# power_board_uC.net
KiCad netlist of a schematic drawn in Altium Designer
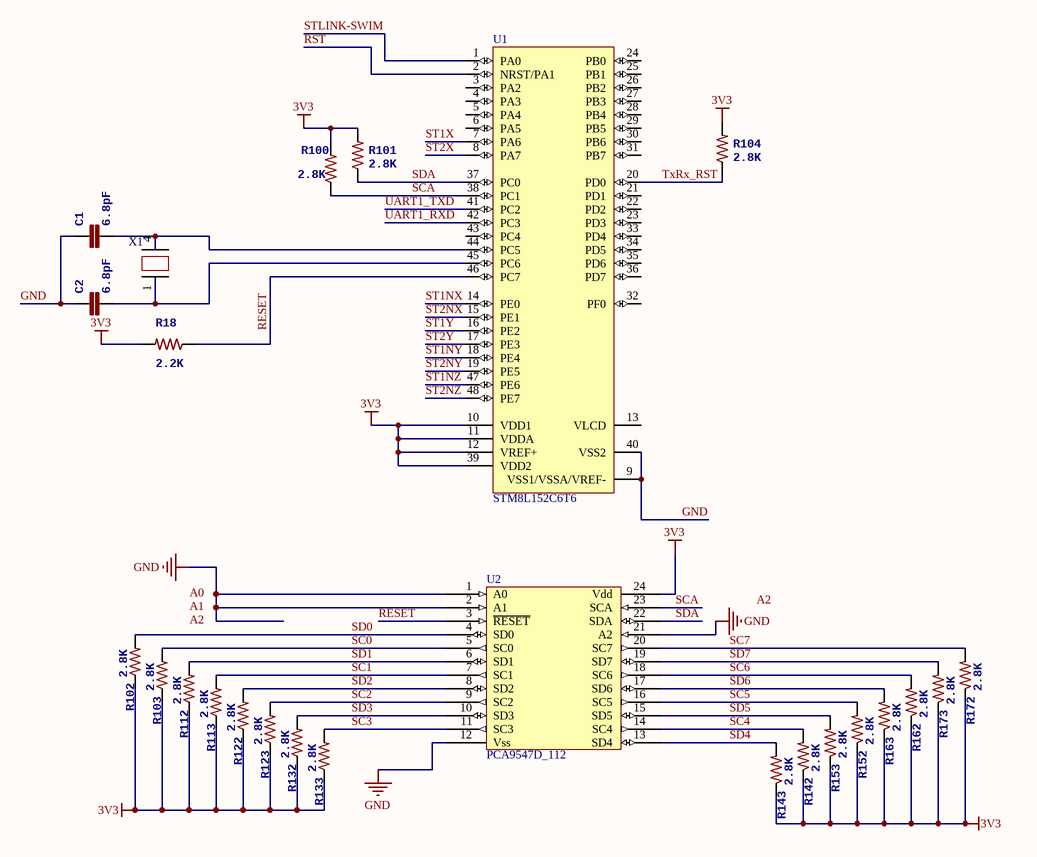
[diagram p0: power_board_uC.SchDoc]

(export (version "E")
  (design (tool "Eeschema 10.0.6"))
  (components
    (comp (ref "C1")
      (value "6.8pF")
      (footprint "0402-CAP")
      (libsource (lib "yusend_power") (part "CAP0402-6_8pF"))
    )
    (comp (ref "C2")
      (value "6.8pF")
      (footprint "0402-CAP")
      (libsource (lib "yusend_power") (part "CAP0402-6_8pF"))
    )
    (comp (ref "R18")
      (value "2.2K")
      (footprint "0805")
      (fields
        (field (name "MANUFACTURER") "TE Connectivity")
        (field (name "MANUFACTURER PART NUMBER") "1625856-2")
        (field (name "TOLERANCE") "±10%")
      )
      (libsource (lib "yusend_power") (part "RES_0805_2k2"))
    )
    (comp (ref "R100")
      (value "2.8K")
      (footprint "0805")
      (fields
        (field (name "MANUFACTURER") "TE Connectivity")
        (field (name "MANUFACTURER PART NUMBER") "1625856-2")
        (field (name "TOLERANCE") "±10%")
      )
      (libsource (lib "yusend_power") (part "RES_0805_2k8"))
    )
    (comp (ref "R101")
      (value "2.8K")
      (footprint "0805")
      (fields
        (field (name "MANUFACTURER") "TE Connectivity")
        (field (name "MANUFACTURER PART NUMBER") "1625856-2")
        (field (name "TOLERANCE") "±10%")
      )
      (libsource (lib "yusend_power") (part "RES_0805_2k8"))
    )
    (comp (ref "R102")
      (value "2.8K")
      (footprint "0805")
      (fields
        (field (name "MANUFACTURER") "TE Connectivity")
        (field (name "MANUFACTURER PART NUMBER") "1625856-2")
        (field (name "TOLERANCE") "±10%")
      )
      (libsource (lib "yusend_power") (part "RES_0805_2k8"))
    )
    (comp (ref "R103")
      (value "2.8K")
      (footprint "0805")
      (fields
        (field (name "MANUFACTURER") "TE Connectivity")
        (field (name "MANUFACTURER PART NUMBER") "1625856-2")
        (field (name "TOLERANCE") "±10%")
      )
      (libsource (lib "yusend_power") (part "RES_0805_2k8"))
    )
    (comp (ref "R104")
      (value "2.8K")
      (footprint "0805")
      (fields
        (field (name "MANUFACTURER") "TE Connectivity")
        (field (name "MANUFACTURER PART NUMBER") "1625856-2")
        (field (name "TOLERANCE") "±10%")
      )
      (libsource (lib "yusend_power") (part "RES_0805_2k8"))
    )
    (comp (ref "R112")
      (value "2.8K")
      (footprint "0805")
      (fields
        (field (name "MANUFACTURER") "TE Connectivity")
        (field (name "MANUFACTURER PART NUMBER") "1625856-2")
        (field (name "TOLERANCE") "±10%")
      )
      (libsource (lib "yusend_power") (part "RES_0805_2k8"))
    )
    (comp (ref "R113")
      (value "2.8K")
      (footprint "0805")
      (fields
        (field (name "MANUFACTURER") "TE Connectivity")
        (field (name "MANUFACTURER PART NUMBER") "1625856-2")
        (field (name "TOLERANCE") "±10%")
      )
      (libsource (lib "yusend_power") (part "RES_0805_2k8"))
    )
    (comp (ref "R122")
      (value "2.8K")
      (footprint "0805")
      (fields
        (field (name "MANUFACTURER") "TE Connectivity")
        (field (name "MANUFACTURER PART NUMBER") "1625856-2")
        (field (name "TOLERANCE") "±10%")
      )
      (libsource (lib "yusend_power") (part "RES_0805_2k8"))
    )
    (comp (ref "R123")
      (value "2.8K")
      (footprint "0805")
      (fields
        (field (name "MANUFACTURER") "TE Connectivity")
        (field (name "MANUFACTURER PART NUMBER") "1625856-2")
        (field (name "TOLERANCE") "±10%")
      )
      (libsource (lib "yusend_power") (part "RES_0805_2k8"))
    )
    (comp (ref "R132")
      (value "2.8K")
      (footprint "0805")
      (fields
        (field (name "MANUFACTURER") "TE Connectivity")
        (field (name "MANUFACTURER PART NUMBER") "1625856-2")
        (field (name "TOLERANCE") "±10%")
      )
      (libsource (lib "yusend_power") (part "RES_0805_2k8"))
    )
    (comp (ref "R133")
      (value "2.8K")
      (footprint "0805")
      (fields
        (field (name "MANUFACTURER") "TE Connectivity")
        (field (name "MANUFACTURER PART NUMBER") "1625856-2")
        (field (name "TOLERANCE") "±10%")
      )
      (libsource (lib "yusend_power") (part "RES_0805_2k8"))
    )
    (comp (ref "R142")
      (value "2.8K")
      (footprint "0805")
      (fields
        (field (name "MANUFACTURER") "TE Connectivity")
        (field (name "MANUFACTURER PART NUMBER") "1625856-2")
        (field (name "TOLERANCE") "±10%")
      )
      (libsource (lib "yusend_power") (part "RES_0805_2k8"))
    )
    (comp (ref "R143")
      (value "2.8K")
      (footprint "0805")
      (fields
        (field (name "MANUFACTURER") "TE Connectivity")
        (field (name "MANUFACTURER PART NUMBER") "1625856-2")
        (field (name "TOLERANCE") "±10%")
      )
      (libsource (lib "yusend_power") (part "RES_0805_2k8"))
    )
    (comp (ref "R152")
      (value "2.8K")
      (footprint "0805")
      (fields
        (field (name "MANUFACTURER") "TE Connectivity")
        (field (name "MANUFACTURER PART NUMBER") "1625856-2")
        (field (name "TOLERANCE") "±10%")
      )
      (libsource (lib "yusend_power") (part "RES_0805_2k8"))
    )
    (comp (ref "R153")
      (value "2.8K")
      (footprint "0805")
      (fields
        (field (name "MANUFACTURER") "TE Connectivity")
        (field (name "MANUFACTURER PART NUMBER") "1625856-2")
        (field (name "TOLERANCE") "±10%")
      )
      (libsource (lib "yusend_power") (part "RES_0805_2k8"))
    )
    (comp (ref "R162")
      (value "2.8K")
      (footprint "0805")
      (fields
        (field (name "MANUFACTURER") "TE Connectivity")
        (field (name "MANUFACTURER PART NUMBER") "1625856-2")
        (field (name "TOLERANCE") "±10%")
      )
      (libsource (lib "yusend_power") (part "RES_0805_2k8"))
    )
    (comp (ref "R163")
      (value "2.8K")
      (footprint "0805")
      (fields
        (field (name "MANUFACTURER") "TE Connectivity")
        (field (name "MANUFACTURER PART NUMBER") "1625856-2")
        (field (name "TOLERANCE") "±10%")
      )
      (libsource (lib "yusend_power") (part "RES_0805_2k8"))
    )
    (comp (ref "R172")
      (value "2.8K")
      (footprint "0805")
      (fields
        (field (name "MANUFACTURER") "TE Connectivity")
        (field (name "MANUFACTURER PART NUMBER") "1625856-2")
        (field (name "TOLERANCE") "±10%")
      )
      (libsource (lib "yusend_power") (part "RES_0805_2k8"))
    )
    (comp (ref "R173")
      (value "2.8K")
      (footprint "0805")
      (fields
        (field (name "MANUFACTURER") "TE Connectivity")
        (field (name "MANUFACTURER PART NUMBER") "1625856-2")
        (field (name "TOLERANCE") "±10%")
      )
      (libsource (lib "yusend_power") (part "RES_0805_2k8"))
    )
    (comp (ref "U1")
      (value "STM8L152C6T6")
      (footprint "LQFP48_M")
      (libsource (lib "Altium Content Vault") (part "MC-ARM-STM8L152-SQ48"))
    )
    (comp (ref "U2")
      (value "PCA9547D_112")
      (footprint "TSOP65P640X110-24N")
      (libsource (lib "yusend_power") (part "PCA9547D_112"))
    )
    (comp (ref "X1")
      (value "XTAL_32MHz")
      (footprint "SOJ550P350X254-4M")
      (libsource (lib "yusend_power") (part "XTAL_32MHz"))
    )
  )
  (nets
    (net (code "4") (name "/RESET") (class "Default")
      (node (ref "R18") (pin "1") (pinfunction "1_1") (pintype "passive"))
      (node (ref "U1") (pin "46") (pinfunction "PC7_46") (pintype "bidirectional"))
      (node (ref "U2") (pin "3") (pinfunction "~{RESET}_3") (pintype "input"))
    )
    (net (code "5") (name "/RST") (class "Default")
      (node (ref "U1") (pin "2") (pinfunction "NRST/PA1_2") (pintype "bidirectional"))
    )
    (net (code "6") (name "/SC0") (class "Default")
      (node (ref "R103") (pin "2") (pinfunction "2_2") (pintype "passive"))
      (node (ref "U2") (pin "5") (pinfunction "SC0_5") (pintype "output"))
    )
    (net (code "7") (name "/SC1") (class "Default")
      (node (ref "R113") (pin "2") (pinfunction "2_2") (pintype "passive"))
      (node (ref "U2") (pin "7") (pinfunction "SC1_7") (pintype "output"))
    )
    (net (code "8") (name "/SC2") (class "Default")
      (node (ref "R123") (pin "2") (pinfunction "2_2") (pintype "passive"))
      (node (ref "U2") (pin "9") (pinfunction "SC2_9") (pintype "output"))
    )
    (net (code "9") (name "/SC3") (class "Default")
      (node (ref "R133") (pin "2") (pinfunction "2_2") (pintype "passive"))
      (node (ref "U2") (pin "11") (pinfunction "SC3_11") (pintype "output"))
    )
    (net (code "10") (name "/SC4") (class "Default")
      (node (ref "R142") (pin "2") (pinfunction "2_2") (pintype "passive"))
      (node (ref "U2") (pin "14") (pinfunction "SC4_14") (pintype "output"))
    )
    (net (code "11") (name "/SC5") (class "Default")
      (node (ref "R152") (pin "2") (pinfunction "2_2") (pintype "passive"))
      (node (ref "U2") (pin "16") (pinfunction "SC5_16") (pintype "output"))
    )
    (net (code "12") (name "/SC6") (class "Default")
      (node (ref "R162") (pin "2") (pinfunction "2_2") (pintype "passive"))
      (node (ref "U2") (pin "18") (pinfunction "SC6_18") (pintype "output"))
    )
    (net (code "13") (name "/SC7") (class "Default")
      (node (ref "R172") (pin "2") (pinfunction "2_2") (pintype "passive"))
      (node (ref "U2") (pin "20") (pinfunction "SC7_20") (pintype "output"))
    )
    (net (code "14") (name "/SCA") (class "Default")
      (node (ref "R100") (pin "1") (pinfunction "1_1") (pintype "passive"))
      (node (ref "U1") (pin "38") (pinfunction "PC1_38") (pintype "bidirectional"))
      (node (ref "U2") (pin "23") (pinfunction "SCA_23") (pintype "input"))
    )
    (net (code "15") (name "/SD0") (class "Default")
      (node (ref "R102") (pin "2") (pinfunction "2_2") (pintype "passive"))
      (node (ref "U2") (pin "4") (pinfunction "SD0_4") (pintype "bidirectional"))
    )
    (net (code "16") (name "/SD1") (class "Default")
      (node (ref "R112") (pin "2") (pinfunction "2_2") (pintype "passive"))
      (node (ref "U2") (pin "6") (pinfunction "SD1_6") (pintype "bidirectional"))
    )
    (net (code "17") (name "/SD2") (class "Default")
      (node (ref "R122") (pin "2") (pinfunction "2_2") (pintype "passive"))
      (node (ref "U2") (pin "8") (pinfunction "SD2_8") (pintype "bidirectional"))
    )
    (net (code "18") (name "/SD3") (class "Default")
      (node (ref "R132") (pin "2") (pinfunction "2_2") (pintype "passive"))
      (node (ref "U2") (pin "10") (pinfunction "SD3_10") (pintype "bidirectional"))
    )
    (net (code "19") (name "/SD4") (class "Default")
      (node (ref "R143") (pin "2") (pinfunction "2_2") (pintype "passive"))
      (node (ref "U2") (pin "13") (pinfunction "SD4_13") (pintype "bidirectional"))
    )
    (net (code "20") (name "/SD5") (class "Default")
      (node (ref "R153") (pin "2") (pinfunction "2_2") (pintype "passive"))
      (node (ref "U2") (pin "15") (pinfunction "SD5_15") (pintype "bidirectional"))
    )
    (net (code "21") (name "/SD6") (class "Default")
      (node (ref "R163") (pin "2") (pinfunction "2_2") (pintype "passive"))
      (node (ref "U2") (pin "17") (pinfunction "SD6_17") (pintype "bidirectional"))
    )
    (net (code "22") (name "/SD7") (class "Default")
      (node (ref "R173") (pin "2") (pinfunction "2_2") (pintype "passive"))
      (node (ref "U2") (pin "19") (pinfunction "SD7_19") (pintype "bidirectional"))
    )
    (net (code "23") (name "/SDA") (class "Default")
      (node (ref "R101") (pin "1") (pinfunction "1_1") (pintype "passive"))
      (node (ref "U1") (pin "37") (pinfunction "PC0_37") (pintype "bidirectional"))
      (node (ref "U2") (pin "22") (pinfunction "SDA_22") (pintype "bidirectional"))
    )
    (net (code "24") (name "/ST1NX") (class "Default")
      (node (ref "U1") (pin "14") (pinfunction "PE0_14") (pintype "bidirectional"))
    )
    (net (code "25") (name "/ST1NY") (class "Default")
      (node (ref "U1") (pin "18") (pinfunction "PE4_18") (pintype "bidirectional"))
    )
    (net (code "26") (name "/ST1NZ") (class "Default")
      (node (ref "U1") (pin "47") (pinfunction "PE6_47") (pintype "bidirectional"))
    )
    (net (code "27") (name "/ST1X") (class "Default")
      (node (ref "U1") (pin "7") (pinfunction "PA6_7") (pintype "bidirectional"))
    )
    (net (code "28") (name "/ST1Y") (class "Default")
      (node (ref "U1") (pin "16") (pinfunction "PE2_16") (pintype "bidirectional"))
    )
    (net (code "29") (name "/ST2NX") (class "Default")
      (node (ref "U1") (pin "15") (pinfunction "PE1_15") (pintype "bidirectional"))
    )
    (net (code "30") (name "/ST2NY") (class "Default")
      (node (ref "U1") (pin "19") (pinfunction "PE5_19") (pintype "bidirectional"))
    )
    (net (code "31") (name "/ST2NZ") (class "Default")
      (node (ref "U1") (pin "48") (pinfunction "PE7_48") (pintype "bidirectional"))
    )
    (net (code "32") (name "/ST2X") (class "Default")
      (node (ref "U1") (pin "8") (pinfunction "PA7_8") (pintype "bidirectional"))
    )
    (net (code "33") (name "/ST2Y") (class "Default")
      (node (ref "U1") (pin "17") (pinfunction "PE3_17") (pintype "bidirectional"))
    )
    (net (code "34") (name "/STLINK-SWIM") (class "Default")
      (node (ref "U1") (pin "1") (pinfunction "PA0_1") (pintype "bidirectional"))
    )
    (net (code "35") (name "/TxRx_RST") (class "Default")
      (node (ref "R104") (pin "1") (pinfunction "1_1") (pintype "passive"))
      (node (ref "U1") (pin "20") (pinfunction "PD0_20") (pintype "bidirectional"))
    )
    (net (code "36") (name "/UART1_RXD") (class "Default")
      (node (ref "U1") (pin "42") (pinfunction "PC3_42") (pintype "bidirectional"))
    )
    (net (code "37") (name "/UART1_TXD") (class "Default")
      (node (ref "U1") (pin "41") (pinfunction "PC2_41") (pintype "bidirectional"))
    )
    (net (code "38") (name "3V3") (class "Default")
      (node (ref "R100") (pin "2") (pinfunction "2_2") (pintype "passive"))
      (node (ref "R101") (pin "2") (pinfunction "2_2") (pintype "passive"))
      (node (ref "R102") (pin "1") (pinfunction "1_1") (pintype "passive"))
      (node (ref "R103") (pin "1") (pinfunction "1_1") (pintype "passive"))
      (node (ref "R104") (pin "2") (pinfunction "2_2") (pintype "passive"))
      (node (ref "R112") (pin "1") (pinfunction "1_1") (pintype "passive"))
      (node (ref "R113") (pin "1") (pinfunction "1_1") (pintype "passive"))
      (node (ref "R122") (pin "1") (pinfunction "1_1") (pintype "passive"))
      (node (ref "R123") (pin "1") (pinfunction "1_1") (pintype "passive"))
      (node (ref "R132") (pin "1") (pinfunction "1_1") (pintype "passive"))
      (node (ref "R133") (pin "1") (pinfunction "1_1") (pintype "passive"))
      (node (ref "R142") (pin "1") (pinfunction "1_1") (pintype "passive"))
      (node (ref "R143") (pin "1") (pinfunction "1_1") (pintype "passive"))
      (node (ref "R152") (pin "1") (pinfunction "1_1") (pintype "passive"))
      (node (ref "R153") (pin "1") (pinfunction "1_1") (pintype "passive"))
      (node (ref "R162") (pin "1") (pinfunction "1_1") (pintype "passive"))
      (node (ref "R163") (pin "1") (pinfunction "1_1") (pintype "passive"))
      (node (ref "R172") (pin "1") (pinfunction "1_1") (pintype "passive"))
      (node (ref "R173") (pin "1") (pinfunction "1_1") (pintype "passive"))
      (node (ref "R18") (pin "2") (pinfunction "2_2") (pintype "passive"))
      (node (ref "U1") (pin "10") (pinfunction "VDD1_10") (pintype "power_in"))
      (node (ref "U1") (pin "11") (pinfunction "VDDA_11") (pintype "power_in"))
      (node (ref "U1") (pin "12") (pinfunction "VREF+_12") (pintype "power_in"))
      (node (ref "U1") (pin "39") (pinfunction "VDD2_39") (pintype "power_in"))
      (node (ref "U2") (pin "24") (pinfunction "Vdd_24") (pintype "power_in"))
    )
    (net (code "39") (name "GND") (class "Default")
      (node (ref "C1") (pin "1") (pinfunction "1_1") (pintype "passive"))
      (node (ref "C2") (pin "1") (pinfunction "1_1") (pintype "passive"))
      (node (ref "U1") (pin "40") (pinfunction "VSS2_40") (pintype "power_in"))
      (node (ref "U1") (pin "9") (pinfunction "VSS1/VSSA/VREF-_9") (pintype "power_in"))
      (node (ref "U2") (pin "1") (pinfunction "A0_1") (pintype "input"))
      (node (ref "U2") (pin "12") (pinfunction "Vss_12") (pintype "power_in"))
      (node (ref "U2") (pin "2") (pinfunction "A1_2") (pintype "input"))
      (node (ref "U2") (pin "21") (pinfunction "A2_21") (pintype "input"))
    )
    (net (code "40") (name "Net-(U1-PC5)") (class "Default")
      (node (ref "C1") (pin "2") (pinfunction "2_2") (pintype "passive"))
      (node (ref "U1") (pin "44") (pinfunction "PC5_44") (pintype "bidirectional"))
      (node (ref "X1") (pin "4") (pinfunction "4_4") (pintype "passive"))
    )
    (net (code "41") (name "Net-(U1-PC6)") (class "Default")
      (node (ref "C2") (pin "2") (pinfunction "2_2") (pintype "passive"))
      (node (ref "U1") (pin "45") (pinfunction "PC6_45") (pintype "bidirectional"))
      (node (ref "X1") (pin "1") (pinfunction "1_1") (pintype "passive"))
    )
    (net (code "42") (name "unconnected-(U1-PA2-Pad3)") (class "Default")
      (node (ref "U1") (pin "3") (pinfunction "PA2_3") (pintype "bidirectional"))
    )
    (net (code "43") (name "unconnected-(U1-PA3-Pad4)") (class "Default")
      (node (ref "U1") (pin "4") (pinfunction "PA3_4") (pintype "bidirectional"))
    )
    (net (code "44") (name "unconnected-(U1-PA4-Pad5)") (class "Default")
      (node (ref "U1") (pin "5") (pinfunction "PA4_5") (pintype "bidirectional"))
    )
    (net (code "45") (name "unconnected-(U1-PA5-Pad6)") (class "Default")
      (node (ref "U1") (pin "6") (pinfunction "PA5_6") (pintype "bidirectional"))
    )
    (net (code "46") (name "unconnected-(U1-PB0-Pad24)") (class "Default")
      (node (ref "U1") (pin "24") (pinfunction "PB0_24") (pintype "bidirectional"))
    )
    (net (code "47") (name "unconnected-(U1-PB1-Pad25)") (class "Default")
      (node (ref "U1") (pin "25") (pinfunction "PB1_25") (pintype "bidirectional"))
    )
    (net (code "48") (name "unconnected-(U1-PB2-Pad26)") (class "Default")
      (node (ref "U1") (pin "26") (pinfunction "PB2_26") (pintype "bidirectional"))
    )
    (net (code "49") (name "unconnected-(U1-PB3-Pad27)") (class "Default")
      (node (ref "U1") (pin "27") (pinfunction "PB3_27") (pintype "bidirectional"))
    )
    (net (code "50") (name "unconnected-(U1-PB4-Pad28)") (class "Default")
      (node (ref "U1") (pin "28") (pinfunction "PB4_28") (pintype "bidirectional"))
    )
    (net (code "51") (name "unconnected-(U1-PB5-Pad29)") (class "Default")
      (node (ref "U1") (pin "29") (pinfunction "PB5_29") (pintype "bidirectional"))
    )
    (net (code "52") (name "unconnected-(U1-PB6-Pad30)") (class "Default")
      (node (ref "U1") (pin "30") (pinfunction "PB6_30") (pintype "bidirectional"))
    )
    (net (code "53") (name "unconnected-(U1-PB7-Pad31)") (class "Default")
      (node (ref "U1") (pin "31") (pinfunction "PB7_31") (pintype "bidirectional"))
    )
    (net (code "54") (name "unconnected-(U1-PC4-Pad43)") (class "Default")
      (node (ref "U1") (pin "43") (pinfunction "PC4_43") (pintype "bidirectional"))
    )
    (net (code "55") (name "unconnected-(U1-PD1-Pad21)") (class "Default")
      (node (ref "U1") (pin "21") (pinfunction "PD1_21") (pintype "bidirectional"))
    )
    (net (code "56") (name "unconnected-(U1-PD2-Pad22)") (class "Default")
      (node (ref "U1") (pin "22") (pinfunction "PD2_22") (pintype "bidirectional"))
    )
    (net (code "57") (name "unconnected-(U1-PD3-Pad23)") (class "Default")
      (node (ref "U1") (pin "23") (pinfunction "PD3_23") (pintype "bidirectional"))
    )
    (net (code "58") (name "unconnected-(U1-PD4-Pad33)") (class "Default")
      (node (ref "U1") (pin "33") (pinfunction "PD4_33") (pintype "bidirectional"))
    )
    (net (code "59") (name "unconnected-(U1-PD5-Pad34)") (class "Default")
      (node (ref "U1") (pin "34") (pinfunction "PD5_34") (pintype "bidirectional"))
    )
    (net (code "60") (name "unconnected-(U1-PD6-Pad35)") (class "Default")
      (node (ref "U1") (pin "35") (pinfunction "PD6_35") (pintype "bidirectional"))
    )
    (net (code "61") (name "unconnected-(U1-PD7-Pad36)") (class "Default")
      (node (ref "U1") (pin "36") (pinfunction "PD7_36") (pintype "bidirectional"))
    )
    (net (code "62") (name "unconnected-(U1-PF0-Pad32)") (class "Default")
      (node (ref "U1") (pin "32") (pinfunction "PF0_32") (pintype "bidirectional"))
    )
    (net (code "63") (name "unconnected-(U1-VLCD-Pad13)") (class "Default")
      (node (ref "U1") (pin "13") (pinfunction "VLCD_13") (pintype "passive"))
    )
  )
)
